# 9_-STM32F-407_Controller.net
KiCad netlist of a schematic drawn in Altium Designer
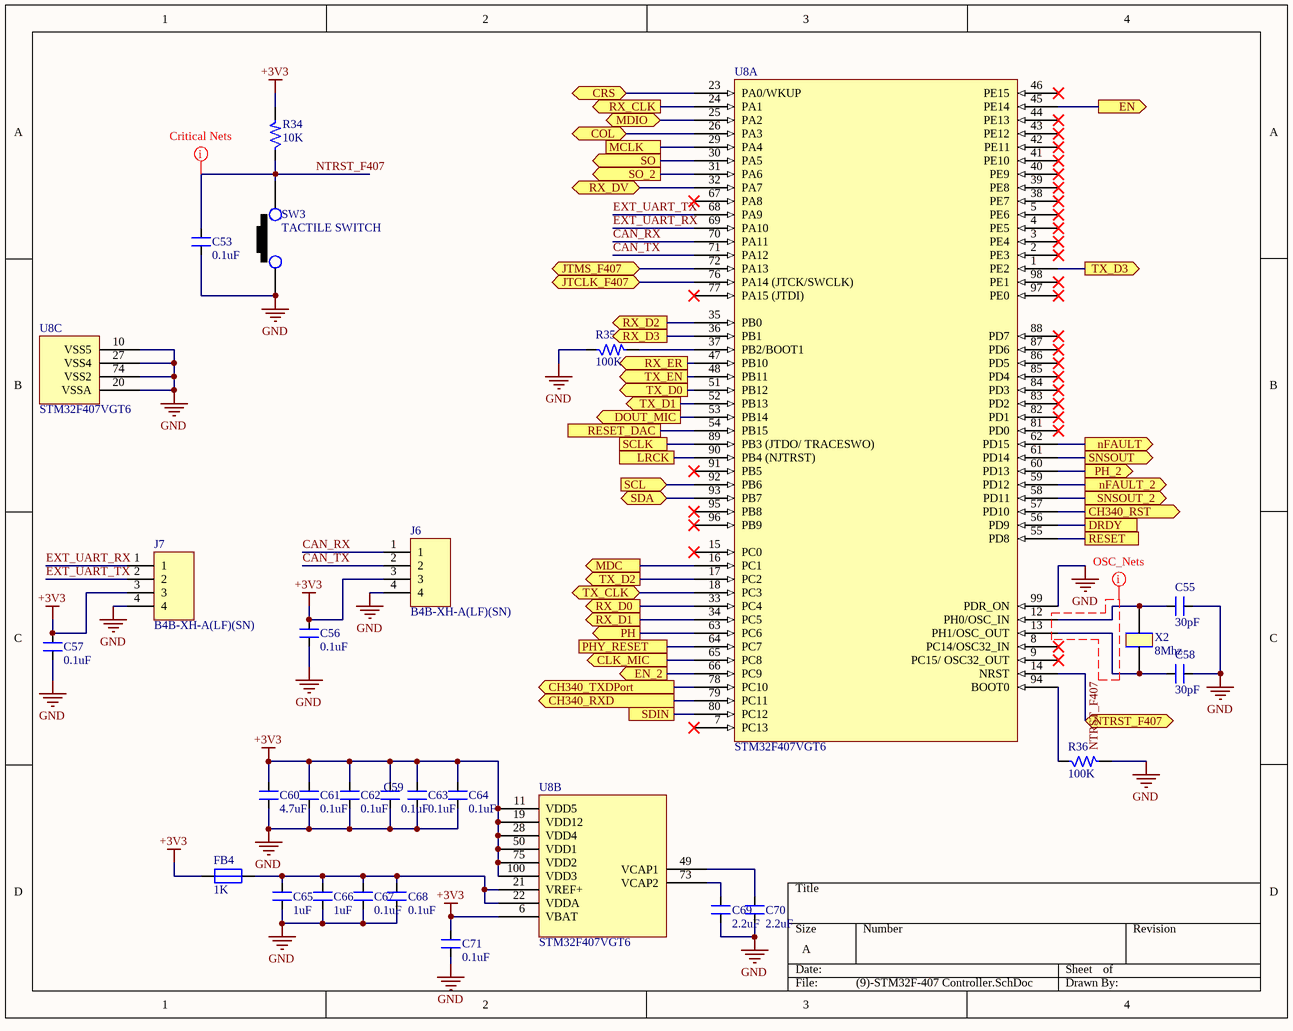
[diagram p0: (9)-STM32F-407 Controller.SchDoc]

(export (version "E")
  (design (tool "Eeschema 10.0.6"))
  (components
    (comp (ref "C53")
      (value "0.1uF")
      (footprint "CAP_0805")
      (description "0.1µF ±10% 50V Ceramic Capacitor X7R 0805 (2012 Metric)")
      (fields
        (field (name "MANUFACTURER") "Samsung")
        (field (name "MANUFACTURER PART NUMBER") "CL21B104KBCNNNC")
      )
      (libsource (lib "ESTEEMPCBLIB") (part "CAP_0.1uF-50V-10%-0805"))
    )
    (comp (ref "C55")
      (value "30pF")
      (footprint "CAP_0805")
      (description "±10% 50V Ceramic Capacitor C0G, NP0 0805 (2012 Metric)")
      (fields
        (field (name "MANUFACTURER PART NUMBER") "C0805C300K5GAC7800")
        (field (name "MANUFACTURER") "KEMET")
      )
      (libsource (lib "ESTEEMPCBLIB") (part "CAP_30pF-50V-10%-0805"))
    )
    (comp (ref "C56")
      (value "0.1uF")
      (footprint "CAP_0805")
      (description "0.1µF ±10% 50V Ceramic Capacitor X7R 0805 (2012 Metric)")
      (fields
        (field (name "MANUFACTURER") "Samsung")
        (field (name "MANUFACTURER PART NUMBER") "CL21B104KBCNNNC")
      )
      (libsource (lib "ESTEEMPCBLIB") (part "CAP_0.1uF-50V-10%-0805"))
    )
    (comp (ref "C57")
      (value "0.1uF")
      (footprint "CAP_0805")
      (description "0.1µF ±10% 50V Ceramic Capacitor X7R 0805 (2012 Metric)")
      (fields
        (field (name "MANUFACTURER") "Samsung")
        (field (name "MANUFACTURER PART NUMBER") "CL21B104KBCNNNC")
      )
      (libsource (lib "ESTEEMPCBLIB") (part "CAP_0.1uF-50V-10%-0805"))
    )
    (comp (ref "C58")
      (value "30pF")
      (footprint "CAP_0805")
      (description "±10% 50V Ceramic Capacitor C0G, NP0 0805 (2012 Metric)")
      (fields
        (field (name "MANUFACTURER PART NUMBER") "C0805C300K5GAC7800")
        (field (name "MANUFACTURER") "KEMET")
      )
      (libsource (lib "ESTEEMPCBLIB") (part "CAP_30pF-50V-10%-0805"))
    )
    (comp (ref "C59")
      (value "0.1uF")
      (footprint "CAP_0805")
      (description "0.1µF ±10% 50V Ceramic Capacitor X7R 0805 (2012 Metric)")
      (fields
        (field (name "MANUFACTURER") "Samsung")
        (field (name "MANUFACTURER PART NUMBER") "CL21B104KBCNNNC")
      )
      (libsource (lib "ESTEEMPCBLIB") (part "CAP_0.1uF-50V-10%-0805"))
    )
    (comp (ref "C60")
      (value "4.7uF")
      (footprint "CAP_0805")
      (description "4.7µF ±10% 50V Ceramic Capacitor X5R 0805 (2012 Metric)")
      (fields
        (field (name "MANUFACTURER") "Yageo")
        (field (name "MANUFACTURER PART NUMBER") "GRM21BR61H475KE51L")
      )
      (libsource (lib "ESTEEMPCBLIB") (part "CAP_4.7uF-50V-10%-0805"))
    )
    (comp (ref "C61")
      (value "0.1uF")
      (footprint "CAP_0805")
      (description "0.1µF ±10% 50V Ceramic Capacitor X7R 0805 (2012 Metric)")
      (fields
        (field (name "MANUFACTURER") "Samsung")
        (field (name "MANUFACTURER PART NUMBER") "CL21B104KBCNNNC")
      )
      (libsource (lib "ESTEEMPCBLIB") (part "CAP_0.1uF-50V-10%-0805"))
    )
    (comp (ref "C62")
      (value "0.1uF")
      (footprint "CAP_0805")
      (description "0.1µF ±10% 50V Ceramic Capacitor X7R 0805 (2012 Metric)")
      (fields
        (field (name "MANUFACTURER") "Samsung")
        (field (name "MANUFACTURER PART NUMBER") "CL21B104KBCNNNC")
      )
      (libsource (lib "ESTEEMPCBLIB") (part "CAP_0.1uF-50V-10%-0805"))
    )
    (comp (ref "C63")
      (value "0.1uF")
      (footprint "CAP_0805")
      (description "0.1µF ±10% 50V Ceramic Capacitor X7R 0805 (2012 Metric)")
      (fields
        (field (name "MANUFACTURER") "Samsung")
        (field (name "MANUFACTURER PART NUMBER") "CL21B104KBCNNNC")
      )
      (libsource (lib "ESTEEMPCBLIB") (part "CAP_0.1uF-50V-10%-0805"))
    )
    (comp (ref "C64")
      (value "0.1uF")
      (footprint "CAP_0805")
      (description "0.1µF ±10% 50V Ceramic Capacitor X7R 0805 (2012 Metric)")
      (fields
        (field (name "MANUFACTURER") "Samsung")
        (field (name "MANUFACTURER PART NUMBER") "CL21B104KBCNNNC")
      )
      (libsource (lib "ESTEEMPCBLIB") (part "CAP_0.1uF-50V-10%-0805"))
    )
    (comp (ref "C65")
      (value "1uF")
      (footprint "CAP_0805")
      (description "1µF ±5% 50V Ceramic Capacitor X7R 0805 (2012 Metric)")
      (fields
        (field (name "MANUFACTURER") "Samsung")
        (field (name "MANUFACTURER PART NUMBER") "CC0805JKX7R9BB105")
      )
      (libsource (lib "ESTEEMPCBLIB") (part "CAP_1uF-50V-5%-0805"))
    )
    (comp (ref "C66")
      (value "1uF")
      (footprint "CAP_0805")
      (description "1µF ±5% 50V Ceramic Capacitor X7R 0805 (2012 Metric)")
      (fields
        (field (name "MANUFACTURER") "Samsung")
        (field (name "MANUFACTURER PART NUMBER") "CC0805JKX7R9BB105")
      )
      (libsource (lib "ESTEEMPCBLIB") (part "CAP_1uF-50V-5%-0805"))
    )
    (comp (ref "C67")
      (value "0.1uF")
      (footprint "CAP_0805")
      (description "0.1µF ±10% 50V Ceramic Capacitor X7R 0805 (2012 Metric)")
      (fields
        (field (name "MANUFACTURER") "Samsung")
        (field (name "MANUFACTURER PART NUMBER") "CL21B104KBCNNNC")
      )
      (libsource (lib "ESTEEMPCBLIB") (part "CAP_0.1uF-50V-10%-0805"))
    )
    (comp (ref "C68")
      (value "0.1uF")
      (footprint "CAP_0805")
      (description "0.1µF ±10% 50V Ceramic Capacitor X7R 0805 (2012 Metric)")
      (fields
        (field (name "MANUFACTURER") "Samsung")
        (field (name "MANUFACTURER PART NUMBER") "CL21B104KBCNNNC")
      )
      (libsource (lib "ESTEEMPCBLIB") (part "CAP_0.1uF-50V-10%-0805"))
    )
    (comp (ref "C69")
      (value "2.2uF")
      (footprint "CAP_0805")
      (description "2.2µF ±10% 25V Ceramic Capacitor X7R 0805 (2012 Metric)")
      (fields
        (field (name "MANUFACTURER") "KEMET")
        (field (name "MANUFACTURER PART NUMBER") "CL21B225KAFNFNE")
      )
      (libsource (lib "ESTEEMPCBLIB") (part "CAP_2.2uF-25V-10%-0805"))
    )
    (comp (ref "C70")
      (value "2.2uF")
      (footprint "CAP_0805")
      (description "2.2µF ±10% 25V Ceramic Capacitor X7R 0805 (2012 Metric)")
      (fields
        (field (name "MANUFACTURER") "KEMET")
        (field (name "MANUFACTURER PART NUMBER") "CL21B225KAFNFNE")
      )
      (libsource (lib "ESTEEMPCBLIB") (part "CAP_2.2uF-25V-10%-0805"))
    )
    (comp (ref "C71")
      (value "0.1uF")
      (footprint "CAP_0805")
      (description "0.1µF ±10% 50V Ceramic Capacitor X7R 0805 (2012 Metric)")
      (fields
        (field (name "MANUFACTURER") "Samsung")
        (field (name "MANUFACTURER PART NUMBER") "CL21B104KBCNNNC")
      )
      (libsource (lib "ESTEEMPCBLIB") (part "CAP_0.1uF-50V-10%-0805"))
    )
    (comp (ref "FB4")
      (value "1K")
      (footprint "IND_0805")
      (description "1 kOhms @ 100MHz 1 Power Line Ferrite Bead 0805 (2012 Metric) 1.6A")
      (fields
        (field (name "MANUFACTURER") "Laird")
        (field (name "MANUFACTURER PART NUMBER") "BLM21SP102SH1D")
      )
      (libsource (lib "ESTEEMPCBLIB") (part "FB_1K-100MHZ-1.6A-0805"))
    )
    (comp (ref "J6")
      (value "B4B-XH-A(LF)(SN)")
      (footprint "CON4_100_B4B-XH-A_TH_ST")
      (description "4 Pins, 1 Row 2.54mm Pitch, straight Connector, male")
      (fields (field (name "MANUFACTURER") "Wurth Electronics") (field (name "MATING PART NUMBER") "XHP-4"))
      (libsource (lib "ESTEEMPCBLIB") (part "CON-PLG_4X1-100-ST-TH"))
    )
    (comp (ref "J7")
      (value "B4B-XH-A(LF)(SN)")
      (footprint "CON4_100_B4B-XH-A_TH_ST")
      (description "4 Pins, 1 Row 2.54mm Pitch, straight Connector, male")
      (fields (field (name "MANUFACTURER") "Wurth Electronics") (field (name "MATING PART NUMBER") "XHP-4"))
      (libsource (lib "ESTEEMPCBLIB") (part "CON-PLG_4X1-100-ST-TH"))
    )
    (comp (ref "R34")
      (value "10K")
      (footprint "RES_0603")
      (description "10 kOhms ±1% 0.1W, 1/10W Chip Resistor 0603 (1608 Metric) Automotive AEC-Q200 Thick Film")
      (fields (field (name "MANUFACTURER") "Walsin") (field (name "MANUFACTURER PART NUMBER") "WR06X1002FTL"))
      (libsource (lib "ESTEEMPCBLIB") (part "RES_10K-0.1W-1%-0603"))
    )
    (comp (ref "R35")
      (value "100K")
      (footprint "RES_0603")
      (description "100 kOhms ±1% 0.1W, 1/10W Chip Resistor 0603 (1608 Metric) Automotive AEC-Q200 Thick Film")
      (fields
        (field (name "MANUFACTURER") "Stackpole Electronics")
        (field (name "MANUFACTURER PART NUMBER") "RMCF0603FT100K")
      )
      (libsource (lib "ESTEEMPCBLIB") (part "RES_100K-0.1W-1%-0603"))
    )
    (comp (ref "R36")
      (value "100K")
      (footprint "RES_0603")
      (description "100 kOhms ±1% 0.1W, 1/10W Chip Resistor 0603 (1608 Metric) Automotive AEC-Q200 Thick Film")
      (fields
        (field (name "MANUFACTURER") "Stackpole Electronics")
        (field (name "MANUFACTURER PART NUMBER") "RMCF0603FT100K")
      )
      (libsource (lib "ESTEEMPCBLIB") (part "RES_100K-0.1W-1%-0603"))
    )
    (comp (ref "SW3")
      (value "TACTILE SWITCH")
      (footprint "SW_342_SMD")
      (description "Tactile Switch SPST-NO Top Actuated Surface Mount")
      (fields
        (field (name "MANUFACTURER") "ITT C&K")
        (field (name "MANUFACTURER PART NUMBER") "RS-282G05A3-SMRT")
      )
      (libsource (lib "ESTEEMPCBLIB") (part "SW1_RS-282G05A3-SMRT-SMD"))
    )
    (comp (ref "U8")
      (value "STM32F407VGT6")
      (footprint "QFN100_19.6_669_58X10_SMD")
      (description "ARM® Cortex®-M4 STM32F4 Microcontroller IC 32-Bit 168MHz 1MB (1M x 8) FLASH 100-LQFP (14x14)")
      (fields (field (name "MANUFACTURER") "STMicroelectronics"))
      (libsource (lib "ESTEEMPCBLIB") (part "IC_STM32F407VGT6"))
    )
    (comp (ref "X2")
      (value "8Mhz")
      (footprint "XTAL_314_240X47_SMD")
      (description "8MHz ±30ppm Crystal 32pF 60 Ohms HC-49/US")
      (fields
        (field (name "MANUFACTURER") "Fox Electronics")
        (field (name "MANUFACTURER PART NUMBER") "ECS-80-32-5PX-TR")
      )
      (libsource (lib "ESTEEMPCBLIB") (part "XTAL_8MHZ-ECS-80-32-5PX-SMD"))
    )
  )
  (nets
    (net (code "1") (name "+3V3") (class "Default")
      (node (ref "C56") (pin "2") (pinfunction "2_2") (pintype "passive"))
      (node (ref "C57") (pin "2") (pinfunction "2_2") (pintype "passive"))
      (node (ref "C59") (pin "1") (pinfunction "1_1") (pintype "passive"))
      (node (ref "C60") (pin "1") (pinfunction "1_1") (pintype "passive"))
      (node (ref "C61") (pin "1") (pinfunction "1_1") (pintype "passive"))
      (node (ref "C62") (pin "1") (pinfunction "1_1") (pintype "passive"))
      (node (ref "C63") (pin "1") (pinfunction "1_1") (pintype "passive"))
      (node (ref "C64") (pin "1") (pinfunction "1_1") (pintype "passive"))
      (node (ref "C71") (pin "1") (pinfunction "1_1") (pintype "passive"))
      (node (ref "FB4") (pin "1") (pinfunction "1_1") (pintype "passive"))
      (node (ref "J6") (pin "3") (pinfunction "3_3") (pintype "passive"))
      (node (ref "J7") (pin "3") (pinfunction "3_3") (pintype "passive"))
      (node (ref "R34") (pin "2") (pinfunction "2_2") (pintype "passive"))
      (node (ref "U8") (pin "100") (pinfunction "VDD3_100") (pintype "passive"))
      (node (ref "U8") (pin "11") (pinfunction "VDD5_11") (pintype "passive"))
      (node (ref "U8") (pin "19") (pinfunction "VDD12_19") (pintype "passive"))
      (node (ref "U8") (pin "28") (pinfunction "VDD4_28") (pintype "passive"))
      (node (ref "U8") (pin "50") (pinfunction "VDD1_50") (pintype "passive"))
      (node (ref "U8") (pin "6") (pinfunction "VBAT_6") (pintype "passive"))
      (node (ref "U8") (pin "75") (pinfunction "VDD2_75") (pintype "passive"))
    )
    (net (code "2") (name "/CAN_RX") (class "Default")
      (node (ref "J6") (pin "1") (pinfunction "1_1") (pintype "passive"))
      (node (ref "U8") (pin "70") (pinfunction "PA11_70") (pintype "input"))
    )
    (net (code "3") (name "/CAN_TX") (class "Default")
      (node (ref "J6") (pin "2") (pinfunction "2_2") (pintype "passive"))
      (node (ref "U8") (pin "71") (pinfunction "PA12_71") (pintype "input"))
    )
    (net (code "4") (name "/CH340_RST") (class "Default")
      (node (ref "U8") (pin "57") (pinfunction "PD10_57") (pintype "input"))
    )
    (net (code "5") (name "/CH340_RXD") (class "Default")
      (node (ref "U8") (pin "79") (pinfunction "PC11_79") (pintype "input"))
    )
    (net (code "6") (name "/CH340_TXDPort") (class "Default")
      (node (ref "U8") (pin "78") (pinfunction "PC10_78") (pintype "input"))
    )
    (net (code "7") (name "/CLK_MIC") (class "Default")
      (node (ref "U8") (pin "65") (pinfunction "PC8_65") (pintype "input"))
    )
    (net (code "8") (name "/COL") (class "Default")
      (node (ref "U8") (pin "26") (pinfunction "PA3_26") (pintype "input"))
    )
    (net (code "9") (name "/CRS") (class "Default")
      (node (ref "U8") (pin "23") (pinfunction "PA0/WKUP_23") (pintype "input"))
    )
    (net (code "10") (name "/DOUT_MIC") (class "Default")
      (node (ref "U8") (pin "53") (pinfunction "PB14_53") (pintype "input"))
    )
    (net (code "11") (name "/DRDY") (class "Default")
      (node (ref "U8") (pin "56") (pinfunction "PD9_56") (pintype "input"))
    )
    (net (code "12") (name "/EN") (class "Default")
      (node (ref "U8") (pin "45") (pinfunction "PE14_45") (pintype "input"))
    )
    (net (code "13") (name "/EN_2") (class "Default")
      (node (ref "U8") (pin "66") (pinfunction "PC9_66") (pintype "input"))
    )
    (net (code "14") (name "/EXT_UART_RX") (class "Default")
      (node (ref "J7") (pin "1") (pinfunction "1_1") (pintype "passive"))
      (node (ref "U8") (pin "69") (pinfunction "PA10_69") (pintype "input"))
    )
    (net (code "15") (name "/EXT_UART_TX") (class "Default")
      (node (ref "J7") (pin "2") (pinfunction "2_2") (pintype "passive"))
      (node (ref "U8") (pin "68") (pinfunction "PA9_68") (pintype "input"))
    )
    (net (code "16") (name "/JTCLK_F407") (class "Default")
      (node (ref "U8") (pin "76") (pinfunction "PA14_(JTCK/SWCLK)_76") (pintype "input"))
    )
    (net (code "17") (name "/JTMS_F407") (class "Default")
      (node (ref "U8") (pin "72") (pinfunction "PA13_72") (pintype "input"))
    )
    (net (code "18") (name "/LRCK") (class "Default")
      (node (ref "U8") (pin "90") (pinfunction "PB4_(NJTRST)_90") (pintype "input"))
    )
    (net (code "19") (name "/MCLK") (class "Default")
      (node (ref "U8") (pin "29") (pinfunction "PA4_29") (pintype "input"))
    )
    (net (code "20") (name "/MDC") (class "Default")
      (node (ref "U8") (pin "16") (pinfunction "PC1_16") (pintype "input"))
    )
    (net (code "21") (name "/MDIO") (class "Default")
      (node (ref "U8") (pin "25") (pinfunction "PA2_25") (pintype "input"))
    )
    (net (code "22") (name "/NTRST_F407") (class "Default")
      (node (ref "C53") (pin "2") (pinfunction "2_2") (pintype "passive"))
      (node (ref "R34") (pin "1") (pinfunction "1_1") (pintype "passive"))
      (node (ref "SW3") (pin "2") (pinfunction "2_2") (pintype "passive"))
      (node (ref "U8") (pin "14") (pinfunction "NRST_14") (pintype "input"))
    )
    (net (code "23") (name "/PH") (class "Default")
      (node (ref "U8") (pin "63") (pinfunction "PC6_63") (pintype "input"))
    )
    (net (code "24") (name "/PHY_RESET") (class "Default")
      (node (ref "U8") (pin "64") (pinfunction "PC7_64") (pintype "input"))
    )
    (net (code "25") (name "/PH_2") (class "Default")
      (node (ref "U8") (pin "60") (pinfunction "PD13_60") (pintype "input"))
    )
    (net (code "26") (name "/RESET") (class "Default")
      (node (ref "U8") (pin "55") (pinfunction "PD8_55") (pintype "input"))
    )
    (net (code "27") (name "/RESET_DAC") (class "Default")
      (node (ref "U8") (pin "54") (pinfunction "PB15_54") (pintype "input"))
    )
    (net (code "28") (name "/RX_CLK") (class "Default")
      (node (ref "U8") (pin "24") (pinfunction "PA1_24") (pintype "input"))
    )
    (net (code "29") (name "/RX_D0") (class "Default")
      (node (ref "U8") (pin "33") (pinfunction "PC4_33") (pintype "input"))
    )
    (net (code "30") (name "/RX_D1") (class "Default")
      (node (ref "U8") (pin "34") (pinfunction "PC5_34") (pintype "input"))
    )
    (net (code "31") (name "/RX_D2") (class "Default")
      (node (ref "U8") (pin "35") (pinfunction "PB0_35") (pintype "input"))
    )
    (net (code "32") (name "/RX_D3") (class "Default")
      (node (ref "U8") (pin "36") (pinfunction "PB1_36") (pintype "input"))
    )
    (net (code "33") (name "/RX_DV") (class "Default")
      (node (ref "U8") (pin "32") (pinfunction "PA7_32") (pintype "input"))
    )
    (net (code "34") (name "/RX_ER") (class "Default")
      (node (ref "U8") (pin "47") (pinfunction "PB10_47") (pintype "input"))
    )
    (net (code "35") (name "/SCL") (class "Default")
      (node (ref "U8") (pin "92") (pinfunction "PB6_92") (pintype "input"))
    )
    (net (code "36") (name "/SCLK") (class "Default")
      (node (ref "U8") (pin "89") (pinfunction "PB3_(JTDO/_TRACESWO)_89") (pintype "input"))
    )
    (net (code "37") (name "/SDA") (class "Default")
      (node (ref "U8") (pin "93") (pinfunction "PB7_93") (pintype "input"))
    )
    (net (code "38") (name "/SDIN") (class "Default")
      (node (ref "U8") (pin "80") (pinfunction "PC12_80") (pintype "input"))
    )
    (net (code "39") (name "/SNSOUT") (class "Default")
      (node (ref "U8") (pin "61") (pinfunction "PD14_61") (pintype "input"))
    )
    (net (code "40") (name "/SNSOUT_2") (class "Default")
      (node (ref "U8") (pin "58") (pinfunction "PD11_58") (pintype "input"))
    )
    (net (code "41") (name "/SO") (class "Default")
      (node (ref "U8") (pin "30") (pinfunction "PA5_30") (pintype "input"))
    )
    (net (code "42") (name "/SO_2") (class "Default")
      (node (ref "U8") (pin "31") (pinfunction "PA6_31") (pintype "input"))
    )
    (net (code "43") (name "/TX_CLK") (class "Default")
      (node (ref "U8") (pin "18") (pinfunction "PC3_18") (pintype "input"))
    )
    (net (code "44") (name "/TX_D0") (class "Default")
      (node (ref "U8") (pin "51") (pinfunction "PB12_51") (pintype "input"))
    )
    (net (code "45") (name "/TX_D1") (class "Default")
      (node (ref "U8") (pin "52") (pinfunction "PB13_52") (pintype "input"))
    )
    (net (code "46") (name "/TX_D2") (class "Default")
      (node (ref "U8") (pin "17") (pinfunction "PC2_17") (pintype "input"))
    )
    (net (code "47") (name "/TX_D3") (class "Default")
      (node (ref "U8") (pin "1") (pinfunction "PE2_1") (pintype "input"))
    )
    (net (code "48") (name "/TX_EN") (class "Default")
      (node (ref "U8") (pin "48") (pinfunction "PB11_48") (pintype "input"))
    )
    (net (code "49") (name "/nFAULT") (class "Default")
      (node (ref "U8") (pin "62") (pinfunction "PD15_62") (pintype "input"))
    )
    (net (code "50") (name "/nFAULT_2") (class "Default")
      (node (ref "U8") (pin "59") (pinfunction "PD12_59") (pintype "input"))
    )
    (net (code "51") (name "GND") (class "Default")
      (node (ref "C53") (pin "1") (pinfunction "1_1") (pintype "passive"))
      (node (ref "C55") (pin "2") (pinfunction "2_2") (pintype "passive"))
      (node (ref "C56") (pin "1") (pinfunction "1_1") (pintype "passive"))
      (node (ref "C57") (pin "1") (pinfunction "1_1") (pintype "passive"))
      (node (ref "C58") (pin "2") (pinfunction "2_2") (pintype "passive"))
      (node (ref "C59") (pin "2") (pinfunction "2_2") (pintype "passive"))
      (node (ref "C60") (pin "2") (pinfunction "2_2") (pintype "passive"))
      (node (ref "C61") (pin "2") (pinfunction "2_2") (pintype "passive"))
      (node (ref "C62") (pin "2") (pinfunction "2_2") (pintype "passive"))
      (node (ref "C63") (pin "2") (pinfunction "2_2") (pintype "passive"))
      (node (ref "C64") (pin "2") (pinfunction "2_2") (pintype "passive"))
      (node (ref "C65") (pin "2") (pinfunction "2_2") (pintype "passive"))
      (node (ref "C66") (pin "2") (pinfunction "2_2") (pintype "passive"))
      (node (ref "C67") (pin "2") (pinfunction "2_2") (pintype "passive"))
      (node (ref "C68") (pin "2") (pinfunction "2_2") (pintype "passive"))
      (node (ref "C69") (pin "2") (pinfunction "2_2") (pintype "passive"))
      (node (ref "C70") (pin "2") (pinfunction "2_2") (pintype "passive"))
      (node (ref "C71") (pin "2") (pinfunction "2_2") (pintype "passive"))
      (node (ref "J6") (pin "4") (pinfunction "4_4") (pintype "passive"))
      (node (ref "J7") (pin "4") (pinfunction "4_4") (pintype "passive"))
      (node (ref "R35") (pin "1") (pinfunction "1_1") (pintype "passive"))
      (node (ref "R36") (pin "2") (pinfunction "2_2") (pintype "passive"))
      (node (ref "SW3") (pin "1") (pinfunction "1_1") (pintype "passive"))
      (node (ref "U8") (pin "10") (pinfunction "VSS5_10") (pintype "passive"))
      (node (ref "U8") (pin "20") (pinfunction "VSSA_20") (pintype "passive"))
      (node (ref "U8") (pin "27") (pinfunction "VSS4_27") (pintype "passive"))
      (node (ref "U8") (pin "74") (pinfunction "VSS2_74") (pintype "passive"))
      (node (ref "U8") (pin "99") (pinfunction "PDR_ON_99") (pintype "input"))
    )
    (net (code "52") (name "Net-(U8A-BOOT0)") (class "Default")
      (node (ref "R36") (pin "1") (pinfunction "1_1") (pintype "passive"))
      (node (ref "U8") (pin "94") (pinfunction "BOOT0_94") (pintype "input"))
    )
    (net (code "53") (name "Net-(U8A-PB2{slash}BOOT1)") (class "Default")
      (node (ref "R35") (pin "2") (pinfunction "2_2") (pintype "passive"))
      (node (ref "U8") (pin "37") (pinfunction "PB2/BOOT1_37") (pintype "input"))
    )
    (net (code "54") (name "Net-(U8A-PH0{slash}OSC_IN)") (class "Default")
      (node (ref "C55") (pin "1") (pinfunction "1_1") (pintype "passive"))
      (node (ref "U8") (pin "12") (pinfunction "PH0/OSC_IN_12") (pintype "input"))
      (node (ref "X2") (pin "2") (pinfunction "2_2") (pintype "passive"))
    )
    (net (code "55") (name "Net-(U8A-PH1{slash}OSC_OUT)") (class "Default")
      (node (ref "C58") (pin "1") (pinfunction "1_1") (pintype "passive"))
      (node (ref "U8") (pin "13") (pinfunction "PH1/OSC_OUT_13") (pintype "input"))
      (node (ref "X2") (pin "1") (pinfunction "1_1") (pintype "passive"))
    )
    (net (code "56") (name "Net-(U8B-VCAP1)") (class "Default")
      (node (ref "C70") (pin "1") (pinfunction "1_1") (pintype "passive"))
      (node (ref "U8") (pin "49") (pinfunction "VCAP1_49") (pintype "passive"))
    )
    (net (code "57") (name "Net-(U8B-VCAP2)") (class "Default")
      (node (ref "C69") (pin "1") (pinfunction "1_1") (pintype "passive"))
      (node (ref "U8") (pin "73") (pinfunction "VCAP2_73") (pintype "passive"))
    )
    (net (code "58") (name "Net-(U8B-VDDA)") (class "Default")
      (node (ref "C65") (pin "1") (pinfunction "1_1") (pintype "passive"))
      (node (ref "C66") (pin "1") (pinfunction "1_1") (pintype "passive"))
      (node (ref "C67") (pin "1") (pinfunction "1_1") (pintype "passive"))
      (node (ref "C68") (pin "1") (pinfunction "1_1") (pintype "passive"))
      (node (ref "FB4") (pin "2") (pinfunction "2_2") (pintype "passive"))
      (node (ref "U8") (pin "21") (pinfunction "VREF+_21") (pintype "passive"))
      (node (ref "U8") (pin "22") (pinfunction "VDDA_22") (pintype "passive"))
    )
    (net (code "59") (name "unconnected-(U8A-PA8-Pad67)") (class "Default")
      (node (ref "U8") (pin "67") (pinfunction "PA8_67") (pintype "input+no_connect"))
    )
    (net (code "60") (name "unconnected-(U8A-PA15_(JTDI)-Pad77)") (class "Default")
      (node (ref "U8") (pin "77") (pinfunction "PA15_(JTDI)_77") (pintype "input+no_connect"))
    )
    (net (code "61") (name "unconnected-(U8A-PB5-Pad91)") (class "Default")
      (node (ref "U8") (pin "91") (pinfunction "PB5_91") (pintype "input+no_connect"))
    )
    (net (code "62") (name "unconnected-(U8A-PB8-Pad95)") (class "Default")
      (node (ref "U8") (pin "95") (pinfunction "PB8_95") (pintype "input+no_connect"))
    )
    (net (code "63") (name "unconnected-(U8A-PB9-Pad96)") (class "Default")
      (node (ref "U8") (pin "96") (pinfunction "PB9_96") (pintype "input+no_connect"))
    )
    (net (code "64") (name "unconnected-(U8A-PC0-Pad15)") (class "Default")
      (node (ref "U8") (pin "15") (pinfunction "PC0_15") (pintype "input+no_connect"))
    )
    (net (code "65") (name "unconnected-(U8A-PC13-Pad7)") (class "Default")
      (node (ref "U8") (pin "7") (pinfunction "PC13_7") (pintype "input+no_connect"))
    )
    (net (code "66") (name "unconnected-(U8A-PC14{slash}OSC32_IN-Pad8)") (class "Default")
      (node (ref "U8") (pin "8") (pinfunction "PC14/OSC32_IN_8") (pintype "input+no_connect"))
    )
    (net (code "67") (name "unconnected-(U8A-PC15{slash}_OSC32_OUT-Pad9)") (class "Default")
      (node (ref "U8") (pin "9") (pinfunction "PC15/_OSC32_OUT_9") (pintype "input+no_connect"))
    )
    (net (code "68") (name "unconnected-(U8A-PD0-Pad81)") (class "Default")
      (node (ref "U8") (pin "81") (pinfunction "PD0_81") (pintype "input+no_connect"))
    )
    (net (code "69") (name "unconnected-(U8A-PD1-Pad82)") (class "Default")
      (node (ref "U8") (pin "82") (pinfunction "PD1_82") (pintype "input+no_connect"))
    )
    (net (code "70") (name "unconnected-(U8A-PD2-Pad83)") (class "Default")
      (node (ref "U8") (pin "83") (pinfunction "PD2_83") (pintype "input+no_connect"))
    )
    (net (code "71") (name "unconnected-(U8A-PD3-Pad84)") (class "Default")
      (node (ref "U8") (pin "84") (pinfunction "PD3_84") (pintype "input+no_connect"))
    )
    (net (code "72") (name "unconnected-(U8A-PD4-Pad85)") (class "Default")
      (node (ref "U8") (pin "85") (pinfunction "PD4_85") (pintype "input+no_connect"))
    )
    (net (code "73") (name "unconnected-(U8A-PD5-Pad86)") (class "Default")
      (node (ref "U8") (pin "86") (pinfunction "PD5_86") (pintype "input+no_connect"))
    )
    (net (code "74") (name "unconnected-(U8A-PD6-Pad87)") (class "Default")
      (node (ref "U8") (pin "87") (pinfunction "PD6_87") (pintype "input+no_connect"))
    )
    (net (code "75") (name "unconnected-(U8A-PD7-Pad88)") (class "Default")
      (node (ref "U8") (pin "88") (pinfunction "PD7_88") (pintype "input+no_connect"))
    )
    (net (code "76") (name "unconnected-(U8A-PE0-Pad97)") (class "Default")
      (node (ref "U8") (pin "97") (pinfunction "PE0_97") (pintype "input+no_connect"))
    )
    (net (code "77") (name "unconnected-(U8A-PE1-Pad98)") (class "Default")
      (node (ref "U8") (pin "98") (pinfunction "PE1_98") (pintype "input+no_connect"))
    )
    (net (code "78") (name "unconnected-(U8A-PE3-Pad2)") (class "Default")
      (node (ref "U8") (pin "2") (pinfunction "PE3_2") (pintype "input+no_connect"))
    )
    (net (code "79") (name "unconnected-(U8A-PE4-Pad3)") (class "Default")
      (node (ref "U8") (pin "3") (pinfunction "PE4_3") (pintype "input+no_connect"))
    )
    (net (code "80") (name "unconnected-(U8A-PE5-Pad4)") (class "Default")
      (node (ref "U8") (pin "4") (pinfunction "PE5_4") (pintype "input+no_connect"))
    )
    (net (code "81") (name "unconnected-(U8A-PE6-Pad5)") (class "Default")
      (node (ref "U8") (pin "5") (pinfunction "PE6_5") (pintype "input+no_connect"))
    )
    (net (code "82") (name "unconnected-(U8A-PE7-Pad38)") (class "Default")
      (node (ref "U8") (pin "38") (pinfunction "PE7_38") (pintype "input+no_connect"))
    )
    (net (code "83") (name "unconnected-(U8A-PE8-Pad39)") (class "Default")
      (node (ref "U8") (pin "39") (pinfunction "PE8_39") (pintype "input+no_connect"))
    )
    (net (code "84") (name "unconnected-(U8A-PE9-Pad40)") (class "Default")
      (node (ref "U8") (pin "40") (pinfunction "PE9_40") (pintype "input+no_connect"))
    )
    (net (code "85") (name "unconnected-(U8A-PE10-Pad41)") (class "Default")
      (node (ref "U8") (pin "41") (pinfunction "PE10_41") (pintype "input+no_connect"))
    )
    (net (code "86") (name "unconnected-(U8A-PE11-Pad42)") (class "Default")
      (node (ref "U8") (pin "42") (pinfunction "PE11_42") (pintype "input+no_connect"))
    )
    (net (code "87") (name "unconnected-(U8A-PE12-Pad43)") (class "Default")
      (node (ref "U8") (pin "43") (pinfunction "PE12_43") (pintype "input+no_connect"))
    )
    (net (code "88") (name "unconnected-(U8A-PE13-Pad44)") (class "Default")
      (node (ref "U8") (pin "44") (pinfunction "PE13_44") (pintype "input+no_connect"))
    )
    (net (code "89") (name "unconnected-(U8A-PE15-Pad46)") (class "Default")
      (node (ref "U8") (pin "46") (pinfunction "PE15_46") (pintype "input+no_connect"))
    )
  )
)
